# P8X32A_Breakout.net
KiCad netlist of a schematic drawn in EAGLE
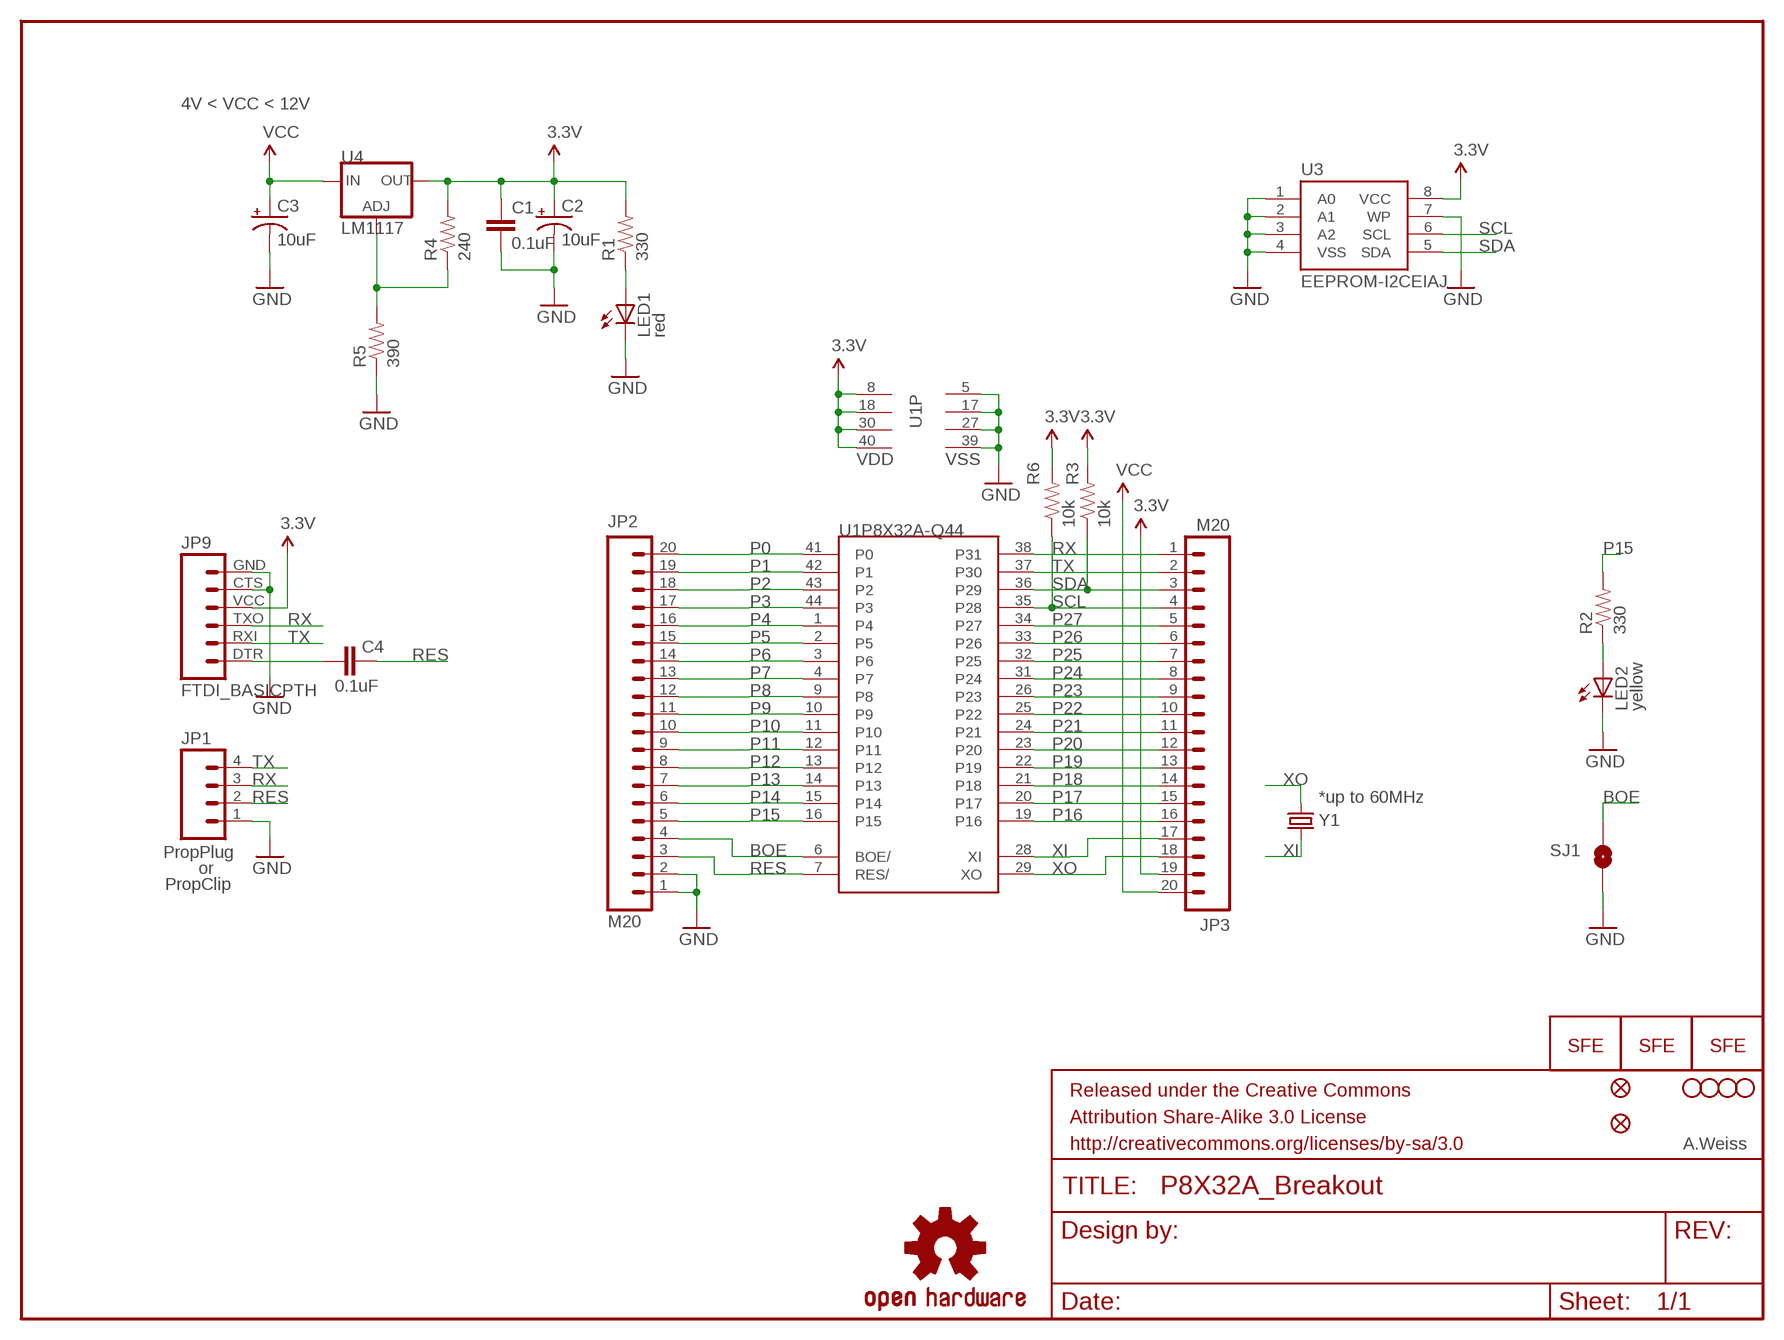
[diagram p0: schematic, sheet 1]

(export (version "E")
  (design (tool "Eeschema 10.0.6"))
  (components
    (comp (ref "C1")
      (value "0.1uF")
      (footprint "eagle-import:0402-CAP")
      (libsource (lib "eagle-import") (part "CAP0402-CAP"))
    )
    (comp (ref "C2")
      (value "10uF")
      (footprint "eagle-import:EIA3216")
      (libsource (lib "eagle-import") (part "CAP_POL1206"))
    )
    (comp (ref "C3")
      (value "10uF")
      (footprint "eagle-import:EIA3216")
      (libsource (lib "eagle-import") (part "CAP_POL1206"))
    )
    (comp (ref "C4")
      (value "0.1uF")
      (footprint "eagle-import:0402-CAP")
      (libsource (lib "eagle-import") (part "CAP0402-CAP"))
    )
    (comp (ref "FRAME1")
      (value "FRAME-LETTER")
      (footprint "eagle-import:CREATIVE_COMMONS")
      (libsource (lib "eagle-import") (part "FRAME-LETTER"))
    )
    (comp (ref "JP1")
      (value "PropPlug")
      (footprint "eagle-import:1X04")
      (libsource (lib "eagle-import") (part "M04PTH"))
    )
    (comp (ref "JP2")
      (value "M20")
      (footprint "eagle-import:1X20")
      (libsource (lib "eagle-import") (part "M20"))
    )
    (comp (ref "JP3")
      (value "M20")
      (footprint "eagle-import:1X20")
      (libsource (lib "eagle-import") (part "M20"))
    )
    (comp (ref "JP4")
      (value "FIDUCIALUFIDUCIAL")
      (footprint "eagle-import:MICRO-FIDUCIAL")
      (libsource (lib "eagle-import") (part "FIDUCIALUFIDUCIAL"))
    )
    (comp (ref "JP5")
      (value "LOGO-SFENEW")
      (footprint "eagle-import:SFE-NEW-WEBLOGO")
      (libsource (lib "eagle-import") (part "LOGO-SFENEW"))
    )
    (comp (ref "JP7")
      (value "LOGO-SFESK")
      (footprint "eagle-import:SFE-LOGO-FLAME")
      (libsource (lib "eagle-import") (part "LOGO-SFESK"))
    )
    (comp (ref "JP9")
      (value "FTDI_BASICPTH")
      (footprint "eagle-import:FTDI_BASIC")
      (libsource (lib "eagle-import") (part "FTDI_BASICPTH"))
    )
    (comp (ref "JP10")
      (value "STAND-OFF")
      (footprint "eagle-import:STAND-OFF")
      (libsource (lib "eagle-import") (part "STAND-OFF"))
    )
    (comp (ref "JP11")
      (value "STAND-OFF")
      (footprint "eagle-import:STAND-OFF")
      (libsource (lib "eagle-import") (part "STAND-OFF"))
    )
    (comp (ref "JP12")
      (value "STAND-OFF")
      (footprint "eagle-import:STAND-OFF")
      (libsource (lib "eagle-import") (part "STAND-OFF"))
    )
    (comp (ref "JP13")
      (value "STAND-OFF")
      (footprint "eagle-import:STAND-OFF")
      (libsource (lib "eagle-import") (part "STAND-OFF"))
    )
    (comp (ref "JP14")
      (value "LOGO-SFENW2")
      (footprint "eagle-import:SFE-NEW-WEB")
      (libsource (lib "eagle-import") (part "LOGO-SFENW2"))
    )
    (comp (ref "JP15")
      (value "FIDUCIALUFIDUCIAL")
      (footprint "eagle-import:MICRO-FIDUCIAL")
      (libsource (lib "eagle-import") (part "FIDUCIALUFIDUCIAL"))
    )
    (comp (ref "LED1")
      (value "red")
      (footprint "eagle-import:LED-0603")
      (libsource (lib "eagle-import") (part "LED0603"))
    )
    (comp (ref "LED2")
      (value "yellow")
      (footprint "eagle-import:LED-0603")
      (libsource (lib "eagle-import") (part "LED0603"))
    )
    (comp (ref "R1")
      (value "330")
      (footprint "eagle-import:0402-RES")
      (libsource (lib "eagle-import") (part "RESISTOR0402-RES"))
    )
    (comp (ref "R2")
      (value "330")
      (footprint "eagle-import:0402-RES")
      (libsource (lib "eagle-import") (part "RESISTOR0402-RES"))
    )
    (comp (ref "R3")
      (value "10k")
      (footprint "eagle-import:0402-RES")
      (libsource (lib "eagle-import") (part "RESISTOR0402-RES"))
    )
    (comp (ref "R4")
      (value "240")
      (footprint "eagle-import:0402-RES")
      (libsource (lib "eagle-import") (part "RESISTOR0402-RES"))
    )
    (comp (ref "R5")
      (value "390")
      (footprint "eagle-import:0402-RES")
      (libsource (lib "eagle-import") (part "RESISTOR0402-RES"))
    )
    (comp (ref "R6")
      (value "10k")
      (footprint "eagle-import:0402-RES")
      (libsource (lib "eagle-import") (part "RESISTOR0402-RES"))
    )
    (comp (ref "SJ1")
      (value "SOLDERJUMPERTRACE")
      (footprint "eagle-import:SJ_2S-TRACE")
      (libsource (lib "eagle-import") (part "SOLDERJUMPERTRACE"))
    )
    (comp (ref "U$1")
      (value "OSHW-LOGOS")
      (footprint "eagle-import:OSHW-LOGO-S")
      (libsource (lib "eagle-import") (part "OSHW-LOGOS"))
    )
    (comp (ref "U1")
      (value "P8X32A-Q44")
      (footprint "eagle-import:P8X32A-Q44")
      (libsource (lib "eagle-import") (part "P8X32A-Q44"))
    )
    (comp (ref "U3")
      (value "EEPROM-I2CEIAJ")
      (footprint "eagle-import:SO08-EIAJ")
      (libsource (lib "eagle-import") (part "EEPROM-I2CEIAJ"))
    )
    (comp (ref "U4")
      (value "V_REG_317SMD")
      (footprint "eagle-import:SOT223")
      (libsource (lib "eagle-import") (part "V_REG_317SMD"))
    )
    (comp (ref "Y1")
      (value "CRYSTALHC49UV")
      (footprint "eagle-import:HC49U-V")
      (libsource (lib "eagle-import") (part "CRYSTALHC49UV"))
    )
  )
  (nets
    (net (code "1") (name "/BOE") (class "Default")
      (node (ref "JP2") (pin "4") (pinfunction "4_4") (pintype "passive"))
      (node (ref "SJ1") (pin "2") (pinfunction "2_2") (pintype "passive"))
      (node (ref "U1") (pin "6") (pinfunction "BOE/_6") (pintype "input"))
    )
    (net (code "2") (name "/P0") (class "Default")
      (node (ref "JP2") (pin "20") (pinfunction "20_20") (pintype "passive"))
      (node (ref "U1") (pin "41") (pinfunction "P0_41") (pintype "bidirectional"))
    )
    (net (code "3") (name "/P1") (class "Default")
      (node (ref "JP2") (pin "19") (pinfunction "19_19") (pintype "passive"))
      (node (ref "U1") (pin "42") (pinfunction "P1_42") (pintype "bidirectional"))
    )
    (net (code "4") (name "/P2") (class "Default")
      (node (ref "JP2") (pin "18") (pinfunction "18_18") (pintype "passive"))
      (node (ref "U1") (pin "43") (pinfunction "P2_43") (pintype "bidirectional"))
    )
    (net (code "5") (name "/P3") (class "Default")
      (node (ref "JP2") (pin "17") (pinfunction "17_17") (pintype "passive"))
      (node (ref "U1") (pin "44") (pinfunction "P3_44") (pintype "bidirectional"))
    )
    (net (code "6") (name "/P4") (class "Default")
      (node (ref "JP2") (pin "16") (pinfunction "16_16") (pintype "passive"))
      (node (ref "U1") (pin "1") (pinfunction "P4_1") (pintype "bidirectional"))
    )
    (net (code "7") (name "/P5") (class "Default")
      (node (ref "JP2") (pin "15") (pinfunction "15_15") (pintype "passive"))
      (node (ref "U1") (pin "2") (pinfunction "P5_2") (pintype "bidirectional"))
    )
    (net (code "8") (name "/P6") (class "Default")
      (node (ref "JP2") (pin "14") (pinfunction "14_14") (pintype "passive"))
      (node (ref "U1") (pin "3") (pinfunction "P6_3") (pintype "bidirectional"))
    )
    (net (code "9") (name "/P7") (class "Default")
      (node (ref "JP2") (pin "13") (pinfunction "13_13") (pintype "passive"))
      (node (ref "U1") (pin "4") (pinfunction "P7_4") (pintype "bidirectional"))
    )
    (net (code "10") (name "/P8") (class "Default")
      (node (ref "JP2") (pin "12") (pinfunction "12_12") (pintype "passive"))
      (node (ref "U1") (pin "9") (pinfunction "P8_9") (pintype "bidirectional"))
    )
    (net (code "11") (name "/P9") (class "Default")
      (node (ref "JP2") (pin "11") (pinfunction "11_11") (pintype "passive"))
      (node (ref "U1") (pin "10") (pinfunction "P9_10") (pintype "bidirectional"))
    )
    (net (code "12") (name "/P10") (class "Default")
      (node (ref "JP2") (pin "10") (pinfunction "10_10") (pintype "passive"))
      (node (ref "U1") (pin "11") (pinfunction "P10_11") (pintype "bidirectional"))
    )
    (net (code "13") (name "/P11") (class "Default")
      (node (ref "JP2") (pin "9") (pinfunction "9_9") (pintype "passive"))
      (node (ref "U1") (pin "12") (pinfunction "P11_12") (pintype "bidirectional"))
    )
    (net (code "14") (name "/P12") (class "Default")
      (node (ref "JP2") (pin "8") (pinfunction "8_8") (pintype "passive"))
      (node (ref "U1") (pin "13") (pinfunction "P12_13") (pintype "bidirectional"))
    )
    (net (code "15") (name "/P13") (class "Default")
      (node (ref "JP2") (pin "7") (pinfunction "7_7") (pintype "passive"))
      (node (ref "U1") (pin "14") (pinfunction "P13_14") (pintype "bidirectional"))
    )
    (net (code "16") (name "/P14") (class "Default")
      (node (ref "JP2") (pin "6") (pinfunction "6_6") (pintype "passive"))
      (node (ref "U1") (pin "15") (pinfunction "P14_15") (pintype "bidirectional"))
    )
    (net (code "17") (name "/P15") (class "Default")
      (node (ref "JP2") (pin "5") (pinfunction "5_5") (pintype "passive"))
      (node (ref "R2") (pin "2") (pinfunction "2_2") (pintype "passive"))
      (node (ref "U1") (pin "16") (pinfunction "P15_16") (pintype "bidirectional"))
    )
    (net (code "18") (name "/P16") (class "Default")
      (node (ref "JP3") (pin "16") (pinfunction "16_16") (pintype "passive"))
      (node (ref "U1") (pin "19") (pinfunction "P16_19") (pintype "bidirectional"))
    )
    (net (code "19") (name "/P17") (class "Default")
      (node (ref "JP3") (pin "15") (pinfunction "15_15") (pintype "passive"))
      (node (ref "U1") (pin "20") (pinfunction "P17_20") (pintype "bidirectional"))
    )
    (net (code "20") (name "/P18") (class "Default")
      (node (ref "JP3") (pin "14") (pinfunction "14_14") (pintype "passive"))
      (node (ref "U1") (pin "21") (pinfunction "P18_21") (pintype "bidirectional"))
    )
    (net (code "21") (name "/P19") (class "Default")
      (node (ref "JP3") (pin "13") (pinfunction "13_13") (pintype "passive"))
      (node (ref "U1") (pin "22") (pinfunction "P19_22") (pintype "bidirectional"))
    )
    (net (code "22") (name "/P20") (class "Default")
      (node (ref "JP3") (pin "12") (pinfunction "12_12") (pintype "passive"))
      (node (ref "U1") (pin "23") (pinfunction "P20_23") (pintype "bidirectional"))
    )
    (net (code "23") (name "/P21") (class "Default")
      (node (ref "JP3") (pin "11") (pinfunction "11_11") (pintype "passive"))
      (node (ref "U1") (pin "24") (pinfunction "P21_24") (pintype "bidirectional"))
    )
    (net (code "24") (name "/P22") (class "Default")
      (node (ref "JP3") (pin "10") (pinfunction "10_10") (pintype "passive"))
      (node (ref "U1") (pin "25") (pinfunction "P22_25") (pintype "bidirectional"))
    )
    (net (code "25") (name "/P23") (class "Default")
      (node (ref "JP3") (pin "9") (pinfunction "9_9") (pintype "passive"))
      (node (ref "U1") (pin "26") (pinfunction "P23_26") (pintype "bidirectional"))
    )
    (net (code "26") (name "/P24") (class "Default")
      (node (ref "JP3") (pin "8") (pinfunction "8_8") (pintype "passive"))
      (node (ref "U1") (pin "31") (pinfunction "P24_31") (pintype "bidirectional"))
    )
    (net (code "27") (name "/P25") (class "Default")
      (node (ref "JP3") (pin "7") (pinfunction "7_7") (pintype "passive"))
      (node (ref "U1") (pin "32") (pinfunction "P25_32") (pintype "bidirectional"))
    )
    (net (code "28") (name "/P26") (class "Default")
      (node (ref "JP3") (pin "6") (pinfunction "6_6") (pintype "passive"))
      (node (ref "U1") (pin "33") (pinfunction "P26_33") (pintype "bidirectional"))
    )
    (net (code "29") (name "/P27") (class "Default")
      (node (ref "JP3") (pin "5") (pinfunction "5_5") (pintype "passive"))
      (node (ref "U1") (pin "34") (pinfunction "P27_34") (pintype "bidirectional"))
    )
    (net (code "30") (name "/RES") (class "Default")
      (node (ref "C4") (pin "2") (pinfunction "2_2") (pintype "passive"))
      (node (ref "JP1") (pin "2") (pinfunction "2_2") (pintype "passive"))
      (node (ref "JP2") (pin "3") (pinfunction "3_3") (pintype "passive"))
      (node (ref "U1") (pin "7") (pinfunction "RES/_7") (pintype "bidirectional"))
    )
    (net (code "31") (name "/RX") (class "Default")
      (node (ref "JP1") (pin "3") (pinfunction "3_3") (pintype "passive"))
      (node (ref "JP3") (pin "1") (pinfunction "1_1") (pintype "passive"))
      (node (ref "JP9") (pin "TXO") (pinfunction "3_TXO") (pintype "passive"))
      (node (ref "U1") (pin "38") (pinfunction "P31_38") (pintype "bidirectional"))
    )
    (net (code "32") (name "/SCL") (class "Default")
      (node (ref "JP3") (pin "4") (pinfunction "4_4") (pintype "passive"))
      (node (ref "R6") (pin "1") (pinfunction "1_1") (pintype "passive"))
      (node (ref "U1") (pin "35") (pinfunction "P28_35") (pintype "bidirectional"))
      (node (ref "U3") (pin "6") (pinfunction "SCL_6") (pintype "bidirectional"))
    )
    (net (code "33") (name "/SDA") (class "Default")
      (node (ref "JP3") (pin "3") (pinfunction "3_3") (pintype "passive"))
      (node (ref "R3") (pin "1") (pinfunction "1_1") (pintype "passive"))
      (node (ref "U1") (pin "36") (pinfunction "P29_36") (pintype "bidirectional"))
      (node (ref "U3") (pin "5") (pinfunction "SDA_5") (pintype "bidirectional"))
    )
    (net (code "34") (name "/TX") (class "Default")
      (node (ref "JP1") (pin "4") (pinfunction "4_4") (pintype "passive"))
      (node (ref "JP3") (pin "2") (pinfunction "2_2") (pintype "passive"))
      (node (ref "JP9") (pin "RXI") (pinfunction "2_RXI") (pintype "passive"))
      (node (ref "U1") (pin "37") (pinfunction "P30_37") (pintype "bidirectional"))
    )
    (net (code "35") (name "/XI") (class "Default")
      (node (ref "JP3") (pin "17") (pinfunction "17_17") (pintype "passive"))
      (node (ref "U1") (pin "28") (pinfunction "XI_28") (pintype "input"))
      (node (ref "Y1") (pin "2") (pinfunction "2_2") (pintype "passive"))
    )
    (net (code "36") (name "/XO") (class "Default")
      (node (ref "JP3") (pin "18") (pinfunction "18_18") (pintype "passive"))
      (node (ref "U1") (pin "29") (pinfunction "XO_29") (pintype "output"))
      (node (ref "Y1") (pin "1") (pinfunction "1_1") (pintype "passive"))
    )
    (net (code "37") (name "3.3V") (class "Default")
      (node (ref "C1") (pin "1") (pinfunction "1_1") (pintype "passive"))
      (node (ref "C2") (pin "A") (pinfunction "+_A") (pintype "passive"))
      (node (ref "JP3") (pin "19") (pinfunction "19_19") (pintype "passive"))
      (node (ref "JP9") (pin "VCC") (pinfunction "4_VCC") (pintype "passive"))
      (node (ref "R1") (pin "2") (pinfunction "2_2") (pintype "passive"))
      (node (ref "R3") (pin "2") (pinfunction "2_2") (pintype "passive"))
      (node (ref "R4") (pin "2") (pinfunction "2_2") (pintype "passive"))
      (node (ref "R6") (pin "2") (pinfunction "2_2") (pintype "passive"))
      (node (ref "U1") (pin "18") (pinfunction "VDD_18") (pintype "power_in"))
      (node (ref "U1") (pin "30") (pinfunction "VDD_30") (pintype "power_in"))
      (node (ref "U1") (pin "40") (pinfunction "VDD_40") (pintype "power_in"))
      (node (ref "U1") (pin "8") (pinfunction "VDD_8") (pintype "power_in"))
      (node (ref "U3") (pin "8") (pinfunction "VCC_8") (pintype "power_in"))
      (node (ref "U4") (pin "2") (pinfunction "OUT_2") (pintype "output"))
    )
    (net (code "38") (name "GND") (class "Default")
      (node (ref "C1") (pin "2") (pinfunction "2_2") (pintype "passive"))
      (node (ref "C2") (pin "C") (pinfunction "-_C") (pintype "passive"))
      (node (ref "C3") (pin "C") (pinfunction "-_C") (pintype "passive"))
      (node (ref "JP1") (pin "1") (pinfunction "1_1") (pintype "passive"))
      (node (ref "JP2") (pin "1") (pinfunction "1_1") (pintype "passive"))
      (node (ref "JP2") (pin "2") (pinfunction "2_2") (pintype "passive"))
      (node (ref "JP9") (pin "CTS") (pinfunction "5_CTS") (pintype "passive"))
      (node (ref "JP9") (pin "GND") (pinfunction "6_GND") (pintype "passive"))
      (node (ref "LED1") (pin "C") (pinfunction "C_C") (pintype "passive"))
      (node (ref "LED2") (pin "C") (pinfunction "C_C") (pintype "passive"))
      (node (ref "R5") (pin "1") (pinfunction "1_1") (pintype "passive"))
      (node (ref "SJ1") (pin "1") (pinfunction "1_1") (pintype "passive"))
      (node (ref "U1") (pin "17") (pinfunction "VSS_17") (pintype "power_in"))
      (node (ref "U1") (pin "27") (pinfunction "VSS_27") (pintype "power_in"))
      (node (ref "U1") (pin "39") (pinfunction "VSS_39") (pintype "power_in"))
      (node (ref "U1") (pin "5") (pinfunction "VSS_5") (pintype "power_in"))
      (node (ref "U3") (pin "1") (pinfunction "A0_1") (pintype "bidirectional"))
      (node (ref "U3") (pin "2") (pinfunction "A1_2") (pintype "bidirectional"))
      (node (ref "U3") (pin "3") (pinfunction "A2_3") (pintype "bidirectional"))
      (node (ref "U3") (pin "4") (pinfunction "VSS_4") (pintype "power_in"))
      (node (ref "U3") (pin "7") (pinfunction "WP_7") (pintype "bidirectional"))
    )
    (net (code "39") (name "Net-(JP9-1)") (class "Default")
      (node (ref "C4") (pin "1") (pinfunction "1_1") (pintype "passive"))
      (node (ref "JP9") (pin "DTR") (pinfunction "1_DTR") (pintype "passive"))
    )
    (net (code "40") (name "Net-(LED1-PadA)") (class "Default")
      (node (ref "LED1") (pin "A") (pinfunction "A_A") (pintype "passive"))
      (node (ref "R1") (pin "1") (pinfunction "1_1") (pintype "passive"))
    )
    (net (code "41") (name "Net-(LED2-PadA)") (class "Default")
      (node (ref "LED2") (pin "A") (pinfunction "A_A") (pintype "passive"))
      (node (ref "R2") (pin "1") (pinfunction "1_1") (pintype "passive"))
    )
    (net (code "42") (name "Net-(U4-ADJ)") (class "Default")
      (node (ref "R4") (pin "1") (pinfunction "1_1") (pintype "passive"))
      (node (ref "R5") (pin "2") (pinfunction "2_2") (pintype "passive"))
      (node (ref "U4") (pin "1") (pinfunction "ADJ_1") (pintype "input"))
    )
    (net (code "43") (name "VCC") (class "Default")
      (node (ref "C3") (pin "A") (pinfunction "+_A") (pintype "passive"))
      (node (ref "JP3") (pin "20") (pinfunction "20_20") (pintype "passive"))
      (node (ref "U4") (pin "3") (pinfunction "IN_3") (pintype "input"))
    )
  )
)
